# nasmini.net
KiCad netlist of a schematic drawn in EAGLE
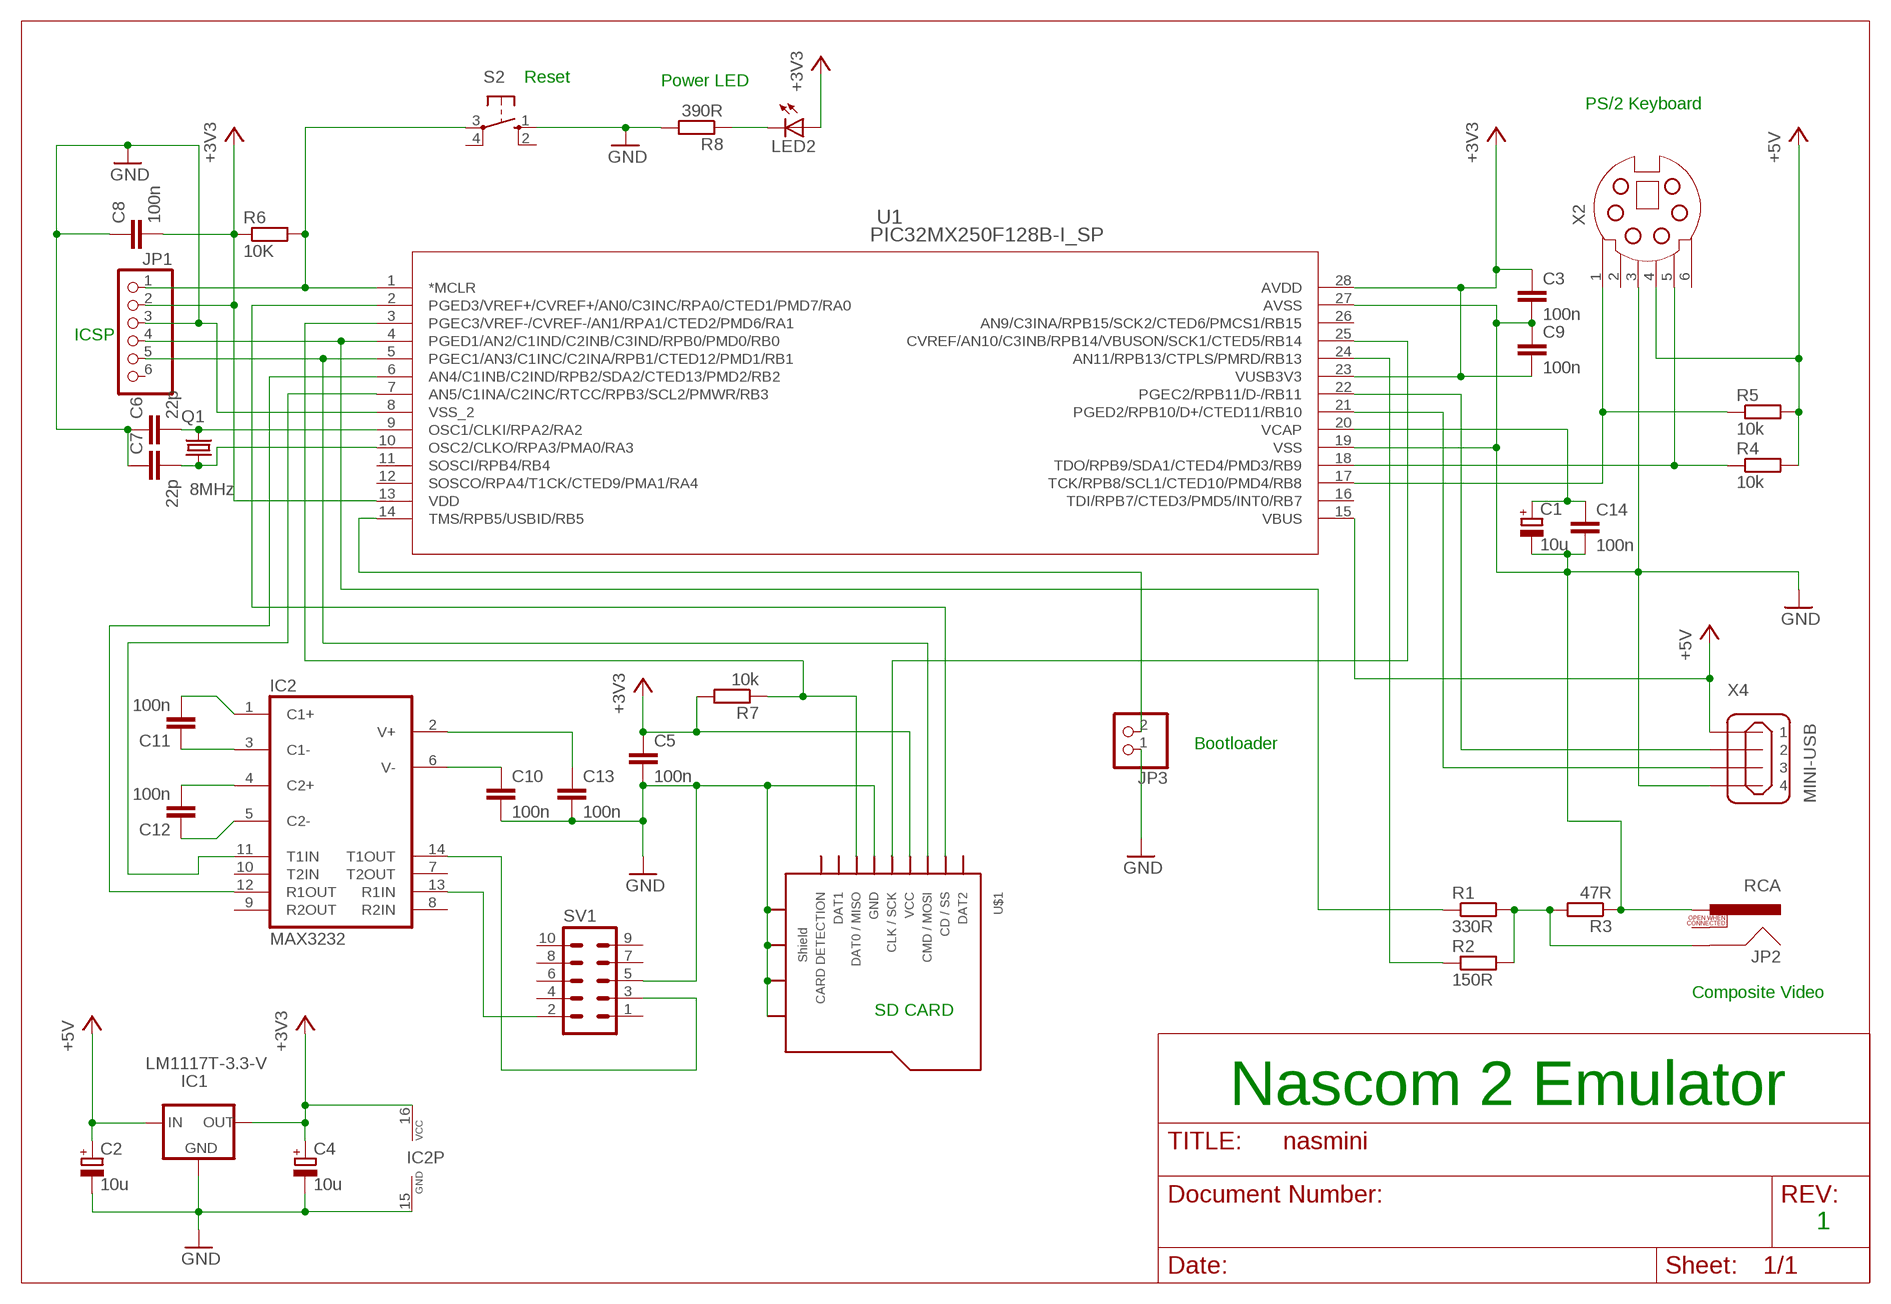
[diagram p0: schematic, sheet 1]

(export (version "E")
  (design (tool "Eeschema 10.0.6"))
  (components
    (comp (ref "C1")
      (value "10u")
      (footprint "eagle-import:E2,5-5")
      (libsource (lib "eagle-import") (part "CPOL-EUE2.5-5"))
    )
    (comp (ref "C2")
      (value "10u")
      (footprint "eagle-import:E2,5-5")
      (libsource (lib "eagle-import") (part "CPOL-EUE2.5-5"))
    )
    (comp (ref "C3")
      (value "100n")
      (footprint "eagle-import:C025-025X050")
      (libsource (lib "eagle-import") (part "C-EU025-025X050"))
    )
    (comp (ref "C4")
      (value "10u")
      (footprint "eagle-import:E2,5-5")
      (libsource (lib "eagle-import") (part "CPOL-EUE2.5-5"))
    )
    (comp (ref "C5")
      (value "100n")
      (footprint "eagle-import:C025-025X050")
      (libsource (lib "eagle-import") (part "C-EU025-025X050"))
    )
    (comp (ref "C6")
      (value "22p")
      (footprint "eagle-import:C025-025X050")
      (libsource (lib "eagle-import") (part "C-EU025-025X050"))
    )
    (comp (ref "C7")
      (value "22p")
      (footprint "eagle-import:C025-025X050")
      (libsource (lib "eagle-import") (part "C-EU025-025X050"))
    )
    (comp (ref "C8")
      (value "100n")
      (footprint "eagle-import:C025-025X050")
      (libsource (lib "eagle-import") (part "C-EU025-025X050"))
    )
    (comp (ref "C9")
      (value "100n")
      (footprint "eagle-import:C025-025X050")
      (libsource (lib "eagle-import") (part "C-EU025-025X050"))
    )
    (comp (ref "C10")
      (value "100n")
      (footprint "eagle-import:C025-025X050")
      (libsource (lib "eagle-import") (part "C-EU025-025X050"))
    )
    (comp (ref "C11")
      (value "100n")
      (footprint "eagle-import:C025-025X050")
      (libsource (lib "eagle-import") (part "C-EU025-025X050"))
    )
    (comp (ref "C12")
      (value "100n")
      (footprint "eagle-import:C025-025X050")
      (libsource (lib "eagle-import") (part "C-EU025-025X050"))
    )
    (comp (ref "C13")
      (value "100n")
      (footprint "eagle-import:C025-025X050")
      (libsource (lib "eagle-import") (part "C-EU025-025X050"))
    )
    (comp (ref "C14")
      (value "100n")
      (footprint "eagle-import:C025-025X050")
      (libsource (lib "eagle-import") (part "C-EU025-025X050"))
    )
    (comp (ref "IC1")
      (value "LM1117T-3.3-V")
      (footprint "eagle-import:TO220V")
      (libsource (lib "eagle-import") (part "LM1117T--V3.3"))
    )
    (comp (ref "IC2")
      (value "MAX3232")
      (footprint "eagle-import:DIL16")
      (fields (field (name "MF") "MAXIM") (field (name "MPN") "MAX232ACPE+"))
      (libsource (lib "eagle-import") (part "MAX232"))
    )
    (comp (ref "JP1")
      (value "PINHD-1X6")
      (footprint "eagle-import:1X06")
      (libsource (lib "eagle-import") (part "PINHD-1X6"))
    )
    (comp (ref "JP2")
      (value "RCA")
      (footprint "eagle-import:RCA")
      (libsource (lib "eagle-import") (part "RCA"))
    )
    (comp (ref "JP3")
      (value "PINHD-1X2")
      (footprint "eagle-import:1X02")
      (libsource (lib "eagle-import") (part "PINHD-1X2"))
    )
    (comp (ref "LED2")
      (value "LED3MM")
      (footprint "eagle-import:LED3MM")
      (libsource (lib "eagle-import") (part "LED3MM"))
    )
    (comp (ref "Q1")
      (value "8MHz")
      (footprint "eagle-import:HC49_S")
      (libsource (lib "eagle-import") (part "CRYSTALHC49S"))
    )
    (comp (ref "R1")
      (value "330R")
      (footprint "eagle-import:0207_7")
      (libsource (lib "eagle-import") (part "R-EU_0207/7"))
    )
    (comp (ref "R2")
      (value "150R")
      (footprint "eagle-import:0207_7")
      (libsource (lib "eagle-import") (part "R-EU_0207/7"))
    )
    (comp (ref "R3")
      (value "47R")
      (footprint "eagle-import:0207_7")
      (libsource (lib "eagle-import") (part "R-EU_0207/7"))
    )
    (comp (ref "R4")
      (value "10k")
      (footprint "eagle-import:0207_7")
      (libsource (lib "eagle-import") (part "R-EU_0207/7"))
    )
    (comp (ref "R5")
      (value "10k")
      (footprint "eagle-import:0207_7")
      (libsource (lib "eagle-import") (part "R-EU_0207/7"))
    )
    (comp (ref "R6")
      (value "10K")
      (footprint "eagle-import:0207_7")
      (libsource (lib "eagle-import") (part "R-EU_0207/7"))
    )
    (comp (ref "R7")
      (value "10k")
      (footprint "eagle-import:0207_7")
      (libsource (lib "eagle-import") (part "R-EU_0207/7"))
    )
    (comp (ref "R8")
      (value "390R")
      (footprint "eagle-import:0207_7")
      (libsource (lib "eagle-import") (part "R-EU_0207/7"))
    )
    (comp (ref "S2")
      (value "10-XX")
      (footprint "eagle-import:B3F-10XX")
      (fields (field (name "MPN") "B3F-1000"))
      (libsource (lib "eagle-import") (part "10-XX"))
    )
    (comp (ref "SV1")
      (value "MA05-2")
      (footprint "eagle-import:MA05-2")
      (libsource (lib "eagle-import") (part "MA05-2"))
    )
    (comp (ref "U$1")
      (value "MICROSD_CARD_POLLIN")
      (footprint "eagle-import:MR__-AP_03__")
      (libsource (lib "eagle-import") (part "MICROSD_CARD_POLLIN"))
    )
    (comp (ref "U1")
      (value "PIC32MX250F128B-I_SP")
      (footprint "eagle-import:SPDIP28_300MC")
      (libsource (lib "eagle-import") (part "PIC32MX250F128B-I_SP"))
    )
    (comp (ref "X2")
      (value "MDSSV-F06")
      (footprint "eagle-import:SSV-BC06")
      (libsource (lib "eagle-import") (part "MDSSV-F06"))
    )
    (comp (ref "X4")
      (value "MINI-USB")
      (footprint "eagle-import:85-32006-201-1")
      (libsource (lib "eagle-import") (part "MINI-USB_SHIELD4P-85-32006-201-1"))
    )
  )
  (nets
    (net (code "1") (name "+3V3") (class "Default")
      (node (ref "C3") (pin "1") (pinfunction "1_1") (pintype "passive"))
      (node (ref "C4") (pin "+") (pinfunction "+_+") (pintype "passive"))
      (node (ref "C5") (pin "1") (pinfunction "1_1") (pintype "passive"))
      (node (ref "C8") (pin "2") (pinfunction "2_2") (pintype "passive"))
      (node (ref "C9") (pin "2") (pinfunction "2_2") (pintype "passive"))
      (node (ref "IC1") (pin "2") (pinfunction "OUT_2") (pintype "passive"))
      (node (ref "IC2") (pin "16") (pinfunction "VCC_16") (pintype "power_in"))
      (node (ref "JP1") (pin "2") (pinfunction "2_2") (pintype "passive"))
      (node (ref "LED2") (pin "A") (pinfunction "A_A") (pintype "passive"))
      (node (ref "R6") (pin "1") (pinfunction "1_1") (pintype "passive"))
      (node (ref "R7") (pin "2") (pinfunction "2_2") (pintype "passive"))
      (node (ref "U$1") (pin "VCC") (pinfunction "VCC_VCC") (pintype "bidirectional"))
      (node (ref "U1") (pin "13") (pinfunction "VDD_13") (pintype "power_in"))
      (node (ref "U1") (pin "23") (pinfunction "VUSB3V3_23") (pintype "power_in"))
      (node (ref "U1") (pin "28") (pinfunction "AVDD_28") (pintype "power_in"))
    )
    (net (code "2") (name "+5V") (class "Default")
      (node (ref "C2") (pin "+") (pinfunction "+_+") (pintype "passive"))
      (node (ref "IC1") (pin "3") (pinfunction "IN_3") (pintype "input"))
      (node (ref "R4") (pin "2") (pinfunction "2_2") (pintype "passive"))
      (node (ref "R5") (pin "2") (pinfunction "2_2") (pintype "passive"))
      (node (ref "U1") (pin "15") (pinfunction "VBUS_15") (pintype "power_in"))
      (node (ref "X2") (pin "4") (pinfunction "4_4") (pintype "passive"))
      (node (ref "X4") (pin "1") (pinfunction "1_1") (pintype "passive"))
    )
    (net (code "3") (name "GND") (class "Default")
      (node (ref "C1") (pin "-") (pinfunction "-_-") (pintype "passive"))
      (node (ref "C10") (pin "2") (pinfunction "2_2") (pintype "passive"))
      (node (ref "C13") (pin "2") (pinfunction "2_2") (pintype "passive"))
      (node (ref "C14") (pin "2") (pinfunction "2_2") (pintype "passive"))
      (node (ref "C2") (pin "-") (pinfunction "-_-") (pintype "passive"))
      (node (ref "C3") (pin "2") (pinfunction "2_2") (pintype "passive"))
      (node (ref "C4") (pin "-") (pinfunction "-_-") (pintype "passive"))
      (node (ref "C5") (pin "2") (pinfunction "2_2") (pintype "passive"))
      (node (ref "C6") (pin "1") (pinfunction "1_1") (pintype "passive"))
      (node (ref "C7") (pin "1") (pinfunction "1_1") (pintype "passive"))
      (node (ref "C8") (pin "1") (pinfunction "1_1") (pintype "passive"))
      (node (ref "C9") (pin "1") (pinfunction "1_1") (pintype "passive"))
      (node (ref "IC1") (pin "1") (pinfunction "GND_1") (pintype "input"))
      (node (ref "IC2") (pin "15") (pinfunction "GND_15") (pintype "power_in"))
      (node (ref "JP1") (pin "3") (pinfunction "3_3") (pintype "passive"))
      (node (ref "JP2") (pin "PIN") (pinfunction "PIN_PIN") (pintype "bidirectional"))
      (node (ref "JP3") (pin "1") (pinfunction "1_1") (pintype "passive"))
      (node (ref "R3") (pin "1") (pinfunction "1_1") (pintype "passive"))
      (node (ref "R8") (pin "2") (pinfunction "2_2") (pintype "passive"))
      (node (ref "S2") (pin "1") (pinfunction "S_1") (pintype "passive"))
      (node (ref "SV1") (pin "5") (pinfunction "5_5") (pintype "passive"))
      (node (ref "U$1") (pin "GND") (pinfunction "GND_GND") (pintype "bidirectional"))
      (node (ref "U$1") (pin "SHD_1") (pinfunction "SHD1_SHD_1") (pintype "bidirectional"))
      (node (ref "U$1") (pin "SHD_2") (pinfunction "SHD2_SHD_2") (pintype "bidirectional"))
      (node (ref "U$1") (pin "SHD_3") (pinfunction "SHD3_SHD_3") (pintype "bidirectional"))
      (node (ref "U$1") (pin "SHD_4") (pinfunction "SHD4_SHD_4") (pintype "bidirectional"))
      (node (ref "U1") (pin "19") (pinfunction "VSS_19") (pintype "power_in"))
      (node (ref "U1") (pin "27") (pinfunction "AVSS_27") (pintype "power_in"))
      (node (ref "U1") (pin "8") (pinfunction "VSS_2_8") (pintype "power_in"))
      (node (ref "X2") (pin "3") (pinfunction "3_3") (pintype "passive"))
      (node (ref "X4") (pin "4") (pinfunction "4_4") (pintype "passive"))
    )
    (net (code "4") (name "Net-(IC2A-C1+)") (class "Default")
      (node (ref "C11") (pin "2") (pinfunction "2_2") (pintype "passive"))
      (node (ref "IC2") (pin "1") (pinfunction "C1+_1") (pintype "bidirectional"))
    )
    (net (code "5") (name "Net-(IC2A-C1-)") (class "Default")
      (node (ref "C11") (pin "1") (pinfunction "1_1") (pintype "passive"))
      (node (ref "IC2") (pin "3") (pinfunction "C1-_3") (pintype "bidirectional"))
    )
    (net (code "6") (name "Net-(IC2A-C2+)") (class "Default")
      (node (ref "C12") (pin "2") (pinfunction "2_2") (pintype "passive"))
      (node (ref "IC2") (pin "4") (pinfunction "C2+_4") (pintype "bidirectional"))
    )
    (net (code "7") (name "Net-(IC2A-C2-)") (class "Default")
      (node (ref "C12") (pin "1") (pinfunction "1_1") (pintype "passive"))
      (node (ref "IC2") (pin "5") (pinfunction "C2-_5") (pintype "bidirectional"))
    )
    (net (code "8") (name "Net-(IC2A-R1IN)") (class "Default")
      (node (ref "IC2") (pin "13") (pinfunction "R1IN_13") (pintype "input"))
      (node (ref "SV1") (pin "2") (pinfunction "2_2") (pintype "passive"))
    )
    (net (code "9") (name "Net-(IC2A-R1OUT)") (class "Default")
      (node (ref "IC2") (pin "12") (pinfunction "R1OUT_12") (pintype "output"))
      (node (ref "U1") (pin "6") (pinfunction "AN4/C1INB/C2IND/RPB2/SDA2/CTED13/PMD2/RB2_6") (pintype "bidirectional"))
    )
    (net (code "10") (name "Net-(IC2A-T1IN)") (class "Default")
      (node (ref "IC2") (pin "11") (pinfunction "T1IN_11") (pintype "input"))
      (node (ref "U1") (pin "7") (pinfunction "AN5/C1INA/C2INC/RTCC/RPB3/SCL2/PMWR/RB3_7") (pintype "bidirectional"))
    )
    (net (code "11") (name "Net-(IC2A-T1OUT)") (class "Default")
      (node (ref "IC2") (pin "14") (pinfunction "T1OUT_14") (pintype "output"))
      (node (ref "SV1") (pin "3") (pinfunction "3_3") (pintype "passive"))
    )
    (net (code "12") (name "Net-(IC2A-V+)") (class "Default")
      (node (ref "C13") (pin "1") (pinfunction "1_1") (pintype "passive"))
      (node (ref "IC2") (pin "2") (pinfunction "V+_2") (pintype "bidirectional"))
    )
    (net (code "13") (name "Net-(IC2A-V-)") (class "Default")
      (node (ref "C10") (pin "1") (pinfunction "1_1") (pintype "passive"))
      (node (ref "IC2") (pin "6") (pinfunction "V-_6") (pintype "bidirectional"))
    )
    (net (code "14") (name "Net-(JP2-PadSHELL)") (class "Default")
      (node (ref "JP2") (pin "SHELL") (pinfunction "SHELL_SHELL") (pintype "bidirectional"))
      (node (ref "R1") (pin "2") (pinfunction "2_2") (pintype "passive"))
      (node (ref "R2") (pin "2") (pinfunction "2_2") (pintype "passive"))
      (node (ref "R3") (pin "2") (pinfunction "2_2") (pintype "passive"))
    )
    (net (code "15") (name "Net-(LED2-C)") (class "Default")
      (node (ref "LED2") (pin "K") (pinfunction "C_K") (pintype "passive"))
      (node (ref "R8") (pin "1") (pinfunction "1_1") (pintype "passive"))
    )
    (net (code "16") (name "Net-(S2-P)") (class "Default")
      (node (ref "JP1") (pin "1") (pinfunction "1_1") (pintype "passive"))
      (node (ref "R6") (pin "2") (pinfunction "2_2") (pintype "passive"))
      (node (ref "S2") (pin "3") (pinfunction "P_3") (pintype "passive"))
      (node (ref "U1") (pin "1") (pinfunction "*MCLR_1") (pintype "input"))
    )
    (net (code "17") (name "Net-(U$1-CD{slash}SS)") (class "Default")
      (node (ref "U$1") (pin "DAT3/CS") (pinfunction "CD/SS_DAT3/CS") (pintype "bidirectional"))
      (node (ref "U1") (pin "2") (pinfunction "PGED3/VREF+/CVREF+/AN0/C3INC/RPA0/CTED1/PMD7/RA0_2") (pintype "bidirectional"))
    )
    (net (code "18") (name "Net-(U$1-CLK{slash}SCK)") (class "Default")
      (node (ref "U$1") (pin "CLK") (pinfunction "CLK/SCK_CLK") (pintype "bidirectional"))
      (node (ref "U1") (pin "25") (pinfunction "CVREF/AN10/C3INB/RPB14/VBUSON/SCK1/CTED5/RB14_25") (pintype "bidirectional"))
    )
    (net (code "19") (name "Net-(U$1-CMD{slash}MOSI)") (class "Default")
      (node (ref "JP1") (pin "5") (pinfunction "5_5") (pintype "passive"))
      (node (ref "U$1") (pin "CMD") (pinfunction "CMD/MOSI_CMD") (pintype "bidirectional"))
      (node (ref "U1") (pin "5") (pinfunction "PGEC1/AN3/C1INC/C2INA/RPB1/CTED12/PMD1/RB1_5") (pintype "bidirectional"))
    )
    (net (code "20") (name "Net-(U$1-DAT0{slash}MISO)") (class "Default")
      (node (ref "R7") (pin "1") (pinfunction "1_1") (pintype "passive"))
      (node (ref "U$1") (pin "DAT0") (pinfunction "DAT0/MISO_DAT0") (pintype "bidirectional"))
      (node (ref "U1") (pin "3") (pinfunction "PGEC3/VREF-/CVREF-/AN1/RPA1/CTED2/PMD6/RA1_3") (pintype "bidirectional"))
    )
    (net (code "21") (name "Net-(U1-AN11{slash}RPB13{slash}CTPLS{slash}PMRD{slash}RB13)") (class "Default")
      (node (ref "R2") (pin "1") (pinfunction "1_1") (pintype "passive"))
      (node (ref "U1") (pin "24") (pinfunction "AN11/RPB13/CTPLS/PMRD/RB13_24") (pintype "bidirectional"))
    )
    (net (code "22") (name "Net-(U1-OSC1{slash}CLKI{slash}RPA2{slash}RA2)") (class "Default")
      (node (ref "C6") (pin "2") (pinfunction "2_2") (pintype "passive"))
      (node (ref "Q1") (pin "2") (pinfunction "2_2") (pintype "passive"))
      (node (ref "U1") (pin "9") (pinfunction "OSC1/CLKI/RPA2/RA2_9") (pintype "bidirectional"))
    )
    (net (code "23") (name "Net-(U1-OSC2{slash}CLKO{slash}RPA3{slash}PMA0{slash}RA3)") (class "Default")
      (node (ref "C7") (pin "2") (pinfunction "2_2") (pintype "passive"))
      (node (ref "Q1") (pin "1") (pinfunction "1_1") (pintype "passive"))
      (node (ref "U1") (pin "10") (pinfunction "OSC2/CLKO/RPA3/PMA0/RA3_10") (pintype "bidirectional"))
    )
    (net (code "24") (name "Net-(U1-PGEC2{slash}RPB11{slash}D-{slash}RB11)") (class "Default")
      (node (ref "U1") (pin "22") (pinfunction "PGEC2/RPB11/D-/RB11_22") (pintype "bidirectional"))
      (node (ref "X4") (pin "2") (pinfunction "2_2") (pintype "passive"))
    )
    (net (code "25") (name "Net-(U1-PGED1{slash}AN2{slash}C1IND{slash}C2INB{slash}C3IND{slash}RPB0{slash}PMD0{slash}RB0)") (class "Default")
      (node (ref "JP1") (pin "4") (pinfunction "4_4") (pintype "passive"))
      (node (ref "R1") (pin "1") (pinfunction "1_1") (pintype "passive"))
      (node (ref "U1") (pin "4") (pinfunction "PGED1/AN2/C1IND/C2INB/C3IND/RPB0/PMD0/RB0_4") (pintype "bidirectional"))
    )
    (net (code "26") (name "Net-(U1-PGED2{slash}RPB10{slash}D+{slash}CTED11{slash}RB10)") (class "Default")
      (node (ref "U1") (pin "21") (pinfunction "PGED2/RPB10/D+/CTED11/RB10_21") (pintype "bidirectional"))
      (node (ref "X4") (pin "3") (pinfunction "3_3") (pintype "passive"))
    )
    (net (code "27") (name "Net-(U1-TCK{slash}RPB8{slash}SCL1{slash}CTED10{slash}PMD4{slash}RB8)") (class "Default")
      (node (ref "R5") (pin "1") (pinfunction "1_1") (pintype "passive"))
      (node (ref "U1") (pin "17") (pinfunction "TCK/RPB8/SCL1/CTED10/PMD4/RB8_17") (pintype "bidirectional"))
      (node (ref "X2") (pin "1") (pinfunction "1_1") (pintype "passive"))
    )
    (net (code "28") (name "Net-(U1-TDO{slash}RPB9{slash}SDA1{slash}CTED4{slash}PMD3{slash}RB9)") (class "Default")
      (node (ref "R4") (pin "1") (pinfunction "1_1") (pintype "passive"))
      (node (ref "U1") (pin "18") (pinfunction "TDO/RPB9/SDA1/CTED4/PMD3/RB9_18") (pintype "bidirectional"))
      (node (ref "X2") (pin "5") (pinfunction "5_5") (pintype "passive"))
    )
    (net (code "29") (name "Net-(U1-TMS{slash}RPB5{slash}USBID{slash}RB5)") (class "Default")
      (node (ref "JP3") (pin "2") (pinfunction "2_2") (pintype "passive"))
      (node (ref "U1") (pin "14") (pinfunction "TMS/RPB5/USBID/RB5_14") (pintype "bidirectional"))
    )
    (net (code "30") (name "Net-(U1-VCAP)") (class "Default")
      (node (ref "C1") (pin "+") (pinfunction "+_+") (pintype "passive"))
      (node (ref "C14") (pin "1") (pinfunction "1_1") (pintype "passive"))
      (node (ref "U1") (pin "20") (pinfunction "VCAP_20") (pintype "power_in"))
    )
    (net (code "31") (name "unconnected-(IC2A-R2IN-Pad8)") (class "Default")
      (node (ref "IC2") (pin "8") (pinfunction "R2IN_8") (pintype "input"))
    )
    (net (code "32") (name "unconnected-(IC2A-R2OUT-Pad9)") (class "Default")
      (node (ref "IC2") (pin "9") (pinfunction "R2OUT_9") (pintype "output"))
    )
    (net (code "33") (name "unconnected-(IC2A-T2IN-Pad10)") (class "Default")
      (node (ref "IC2") (pin "10") (pinfunction "T2IN_10") (pintype "input"))
    )
    (net (code "34") (name "unconnected-(IC2A-T2OUT-Pad7)") (class "Default")
      (node (ref "IC2") (pin "7") (pinfunction "T2OUT_7") (pintype "output"))
    )
    (net (code "35") (name "unconnected-(JP1-Pad6)") (class "Default")
      (node (ref "JP1") (pin "6") (pinfunction "6_6") (pintype "passive"))
    )
    (net (code "36") (name "unconnected-(JP2-PadSWITCH)") (class "Default")
      (node (ref "JP2") (pin "SWITCH") (pinfunction "SWITCH_SWITCH") (pintype "bidirectional"))
    )
    (net (code "37") (name "unconnected-(S2-P1-Pad4)") (class "Default")
      (node (ref "S2") (pin "4") (pinfunction "P1_4") (pintype "passive"))
    )
    (net (code "38") (name "unconnected-(S2-S1-Pad2)") (class "Default")
      (node (ref "S2") (pin "2") (pinfunction "S1_2") (pintype "passive"))
    )
    (net (code "39") (name "unconnected-(SV1-Pad1)") (class "Default")
      (node (ref "SV1") (pin "1") (pinfunction "1_1") (pintype "passive"))
    )
    (net (code "40") (name "unconnected-(SV1-Pad4)") (class "Default")
      (node (ref "SV1") (pin "4") (pinfunction "4_4") (pintype "passive"))
    )
    (net (code "41") (name "unconnected-(SV1-Pad6)") (class "Default")
      (node (ref "SV1") (pin "6") (pinfunction "6_6") (pintype "passive"))
    )
    (net (code "42") (name "unconnected-(SV1-Pad7)") (class "Default")
      (node (ref "SV1") (pin "7") (pinfunction "7_7") (pintype "passive"))
    )
    (net (code "43") (name "unconnected-(SV1-Pad8)") (class "Default")
      (node (ref "SV1") (pin "8") (pinfunction "8_8") (pintype "passive"))
    )
    (net (code "44") (name "unconnected-(SV1-Pad9)") (class "Default")
      (node (ref "SV1") (pin "9") (pinfunction "9_9") (pintype "passive"))
    )
    (net (code "45") (name "unconnected-(SV1-Pad10)") (class "Default")
      (node (ref "SV1") (pin "10") (pinfunction "10_10") (pintype "passive"))
    )
    (net (code "46") (name "unconnected-(U$1-CARD_D-PadCARD_DETECTION)") (class "Default")
      (node (ref "U$1") (pin "CARD_DETECTION") (pinfunction "CARD_D_CARD_DETECTION") (pintype "bidirectional"))
    )
    (net (code "47") (name "unconnected-(U$1-PadDAT1)") (class "Default")
      (node (ref "U$1") (pin "DAT1") (pinfunction "DAT1_DAT1") (pintype "bidirectional"))
    )
    (net (code "48") (name "unconnected-(U$1-PadDAT2)") (class "Default")
      (node (ref "U$1") (pin "DAT2") (pinfunction "DAT2_DAT2") (pintype "bidirectional"))
    )
    (net (code "49") (name "unconnected-(U1-AN9{slash}C3INA{slash}RPB15{slash}SCK2{slash}CTED6{slash}PMCS1{slash}RB15-Pad26)") (class "Default")
      (node (ref "U1") (pin "26") (pinfunction "AN9/C3INA/RPB15/SCK2/CTED6/PMCS1/RB15_26") (pintype "bidirectional"))
    )
    (net (code "50") (name "unconnected-(U1-SOSCI{slash}RPB4{slash}RB4-Pad11)") (class "Default")
      (node (ref "U1") (pin "11") (pinfunction "SOSCI/RPB4/RB4_11") (pintype "bidirectional"))
    )
    (net (code "51") (name "unconnected-(U1-SOSCO{slash}RPA4{slash}T1CK{slash}CTED9{slash}PMA1{slash}RA4-Pad12)") (class "Default")
      (node (ref "U1") (pin "12") (pinfunction "SOSCO/RPA4/T1CK/CTED9/PMA1/RA4_12") (pintype "bidirectional"))
    )
    (net (code "52") (name "unconnected-(U1-TDI{slash}RPB7{slash}CTED3{slash}PMD5{slash}INT0{slash}RB7-Pad16)") (class "Default")
      (node (ref "U1") (pin "16") (pinfunction "TDI/RPB7/CTED3/PMD5/INT0/RB7_16") (pintype "bidirectional"))
    )
    (net (code "53") (name "unconnected-(X2-Pad2)") (class "Default")
      (node (ref "X2") (pin "2") (pinfunction "2_2") (pintype "passive"))
    )
    (net (code "54") (name "unconnected-(X2-Pad6)") (class "Default")
      (node (ref "X2") (pin "6") (pinfunction "6_6") (pintype "passive"))
    )
  )
)
